# M_G_ext_step_motor.net
KiCad netlist of a schematic drawn in EAGLE
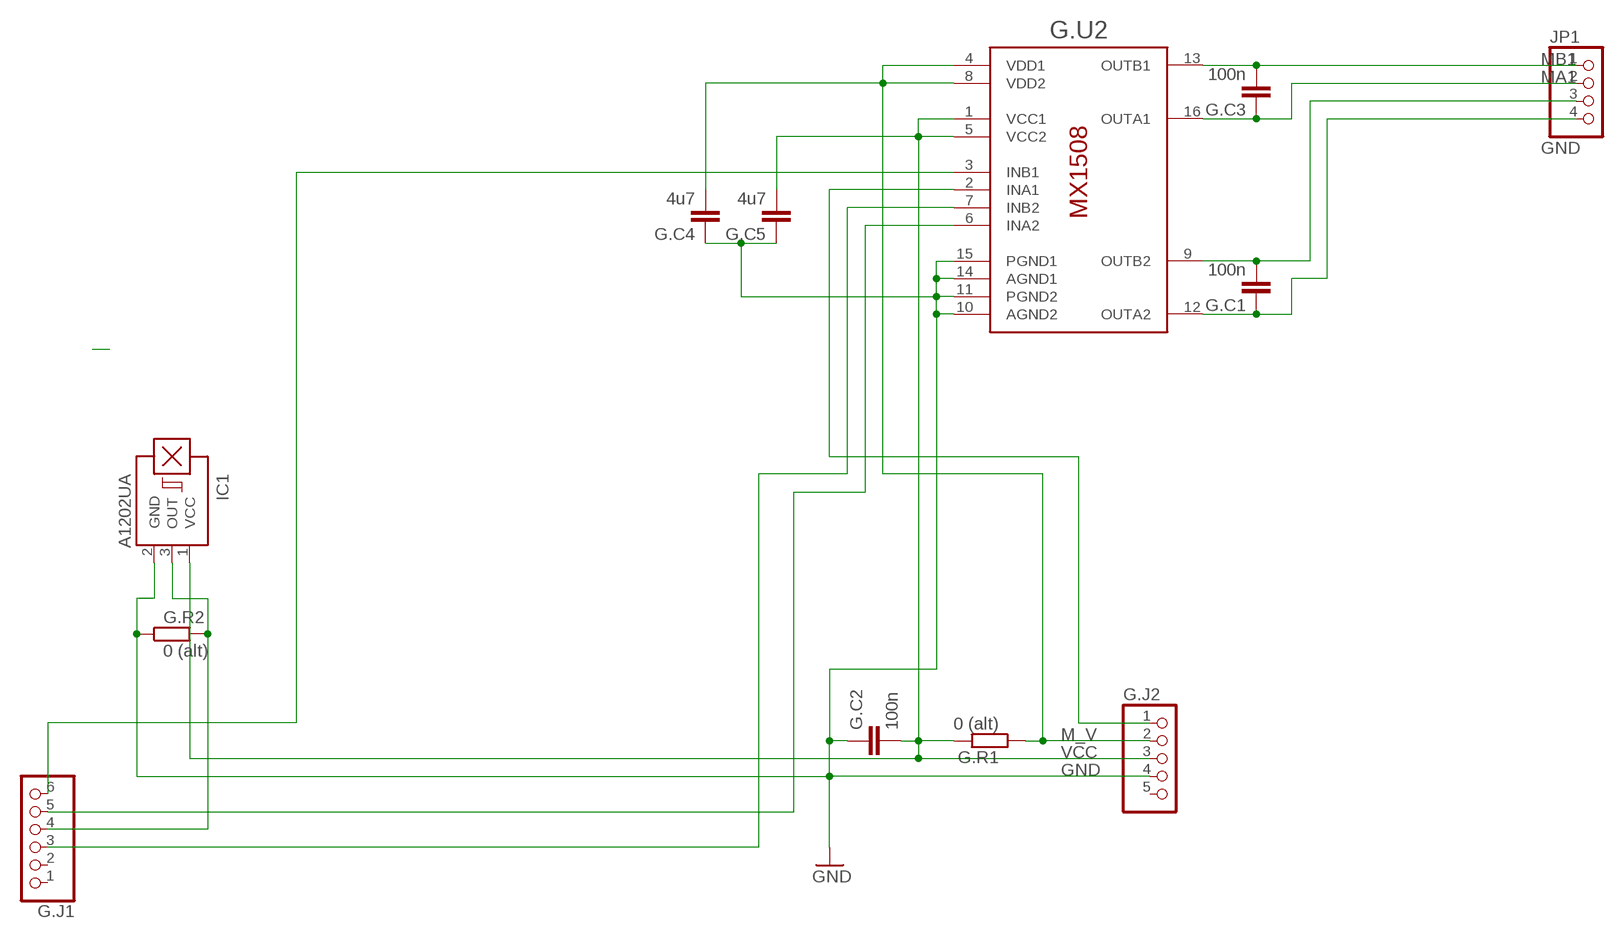
[diagram p0: schematic, sheet 1]

(export (version "E")
  (design (tool "Eeschema 10.0.6"))
  (components
    (comp (ref "G.C1")
      (value "100n")
      (footprint "eagle-import:C0603")
      (libsource (lib "eagle-import") (part "C-EUC0603"))
    )
    (comp (ref "G.C2")
      (value "100n")
      (footprint "eagle-import:C0603")
      (libsource (lib "eagle-import") (part "C-EUC0603"))
    )
    (comp (ref "G.C3")
      (value "100n")
      (footprint "eagle-import:C0603")
      (libsource (lib "eagle-import") (part "C-EUC0603"))
    )
    (comp (ref "G.C4")
      (value "4u7")
      (footprint "eagle-import:C0603")
      (libsource (lib "eagle-import") (part "C-EUC0603"))
    )
    (comp (ref "G.C5")
      (value "4u7")
      (footprint "eagle-import:C0603")
      (libsource (lib "eagle-import") (part "C-EUC0603"))
    )
    (comp (ref "G.J1")
      (value "PINHD-1X6")
      (footprint "eagle-import:1X06")
      (libsource (lib "eagle-import") (part "PINHD-1X6"))
    )
    (comp (ref "G.J2")
      (value "PINHD-1X5")
      (footprint "eagle-import:1X05")
      (libsource (lib "eagle-import") (part "PINHD-1X5"))
    )
    (comp (ref "G.R1")
      (value "0 (alt)")
      (footprint "eagle-import:R0603")
      (libsource (lib "eagle-import") (part "R-EU_R0603"))
    )
    (comp (ref "G.R2")
      (value "0 (alt)")
      (footprint "eagle-import:R0603")
      (libsource (lib "eagle-import") (part "R-EU_R0603"))
    )
    (comp (ref "G.U2")
      (value "MX1508")
      (footprint "eagle-import:SOP16")
      (libsource (lib "eagle-import") (part "MX1508"))
    )
    (comp (ref "IC1")
      (value "A1202UA")
      (footprint "eagle-import:SIP3-UA")
      (libsource (lib "eagle-import") (part "A12?UA02"))
    )
    (comp (ref "JP1")
      (value "PINHD-1X4")
      (footprint "eagle-import:1X04")
      (libsource (lib "eagle-import") (part "PINHD-1X4"))
    )
  )
  (nets
    (net (code "1") (name "/MA1") (class "Default")
      (node (ref "G.C3") (pin "1") (pinfunction "1_1") (pintype "passive"))
      (node (ref "G.U2") (pin "16") (pinfunction "OUTA1_16") (pintype "bidirectional"))
      (node (ref "JP1") (pin "2") (pinfunction "2_2") (pintype "passive"))
    )
    (net (code "2") (name "/MB1") (class "Default")
      (node (ref "G.C3") (pin "2") (pinfunction "2_2") (pintype "passive"))
      (node (ref "G.U2") (pin "13") (pinfunction "OUTB1_13") (pintype "bidirectional"))
      (node (ref "JP1") (pin "1") (pinfunction "1_1") (pintype "passive"))
    )
    (net (code "3") (name "/M_V") (class "Default")
      (node (ref "G.C4") (pin "2") (pinfunction "2_2") (pintype "passive"))
      (node (ref "G.J2") (pin "2") (pinfunction "2_2") (pintype "passive"))
      (node (ref "G.R1") (pin "1") (pinfunction "1_1") (pintype "passive"))
      (node (ref "G.U2") (pin "4") (pinfunction "VDD1_4") (pintype "bidirectional"))
      (node (ref "G.U2") (pin "8") (pinfunction "VDD2_8") (pintype "bidirectional"))
    )
    (net (code "4") (name "/VCC") (class "Default")
      (node (ref "G.C2") (pin "2") (pinfunction "2_2") (pintype "passive"))
      (node (ref "G.C5") (pin "2") (pinfunction "2_2") (pintype "passive"))
      (node (ref "G.J2") (pin "3") (pinfunction "3_3") (pintype "passive"))
      (node (ref "G.R1") (pin "2") (pinfunction "2_2") (pintype "passive"))
      (node (ref "G.U2") (pin "1") (pinfunction "VCC1_1") (pintype "bidirectional"))
      (node (ref "G.U2") (pin "5") (pinfunction "VCC2_5") (pintype "bidirectional"))
      (node (ref "IC1") (pin "1") (pinfunction "VCC_1") (pintype "power_in"))
    )
    (net (code "5") (name "GND") (class "Default")
      (node (ref "G.C2") (pin "1") (pinfunction "1_1") (pintype "passive"))
      (node (ref "G.C4") (pin "1") (pinfunction "1_1") (pintype "passive"))
      (node (ref "G.C5") (pin "1") (pinfunction "1_1") (pintype "passive"))
      (node (ref "G.J2") (pin "4") (pinfunction "4_4") (pintype "passive"))
      (node (ref "G.R2") (pin "1") (pinfunction "1_1") (pintype "passive"))
      (node (ref "G.U2") (pin "10") (pinfunction "AGND2_10") (pintype "bidirectional"))
      (node (ref "G.U2") (pin "11") (pinfunction "PGND2_11") (pintype "bidirectional"))
      (node (ref "G.U2") (pin "14") (pinfunction "AGND1_14") (pintype "bidirectional"))
      (node (ref "G.U2") (pin "15") (pinfunction "PGND1_15") (pintype "bidirectional"))
      (node (ref "IC1") (pin "2") (pinfunction "GND_2") (pintype "power_in"))
    )
    (net (code "6") (name "Net-(G.U2-INA1)") (class "Default")
      (node (ref "G.J2") (pin "1") (pinfunction "1_1") (pintype "passive"))
      (node (ref "G.U2") (pin "2") (pinfunction "INA1_2") (pintype "bidirectional"))
    )
    (net (code "7") (name "Net-(G.U2-INA2)") (class "Default")
      (node (ref "G.J1") (pin "5") (pinfunction "5_5") (pintype "passive"))
      (node (ref "G.U2") (pin "6") (pinfunction "INA2_6") (pintype "bidirectional"))
    )
    (net (code "8") (name "Net-(G.U2-INB1)") (class "Default")
      (node (ref "G.J1") (pin "6") (pinfunction "6_6") (pintype "passive"))
      (node (ref "G.U2") (pin "3") (pinfunction "INB1_3") (pintype "bidirectional"))
    )
    (net (code "9") (name "Net-(G.U2-INB2)") (class "Default")
      (node (ref "G.J1") (pin "3") (pinfunction "3_3") (pintype "passive"))
      (node (ref "G.U2") (pin "7") (pinfunction "INB2_7") (pintype "bidirectional"))
    )
    (net (code "10") (name "Net-(G.U2-OUTA2)") (class "Default")
      (node (ref "G.C1") (pin "1") (pinfunction "1_1") (pintype "passive"))
      (node (ref "G.U2") (pin "12") (pinfunction "OUTA2_12") (pintype "bidirectional"))
      (node (ref "JP1") (pin "4") (pinfunction "4_4") (pintype "passive"))
    )
    (net (code "11") (name "Net-(G.U2-OUTB2)") (class "Default")
      (node (ref "G.C1") (pin "2") (pinfunction "2_2") (pintype "passive"))
      (node (ref "G.U2") (pin "9") (pinfunction "OUTB2_9") (pintype "bidirectional"))
      (node (ref "JP1") (pin "3") (pinfunction "3_3") (pintype "passive"))
    )
    (net (code "12") (name "Net-(IC1-OUT)") (class "Default")
      (node (ref "G.J1") (pin "4") (pinfunction "4_4") (pintype "passive"))
      (node (ref "G.R2") (pin "2") (pinfunction "2_2") (pintype "passive"))
      (node (ref "IC1") (pin "3") (pinfunction "OUT_3") (pintype "output"))
    )
    (net (code "13") (name "unconnected-(G.J1-Pad1)") (class "Default")
      (node (ref "G.J1") (pin "1") (pinfunction "1_1") (pintype "passive"))
    )
    (net (code "14") (name "unconnected-(G.J1-Pad2)") (class "Default")
      (node (ref "G.J1") (pin "2") (pinfunction "2_2") (pintype "passive"))
    )
    (net (code "15") (name "unconnected-(G.J2-Pad5)") (class "Default")
      (node (ref "G.J2") (pin "5") (pinfunction "5_5") (pintype "passive"))
    )
  )
)
